# mosfets.net
KiCad netlist of a schematic drawn in EAGLE
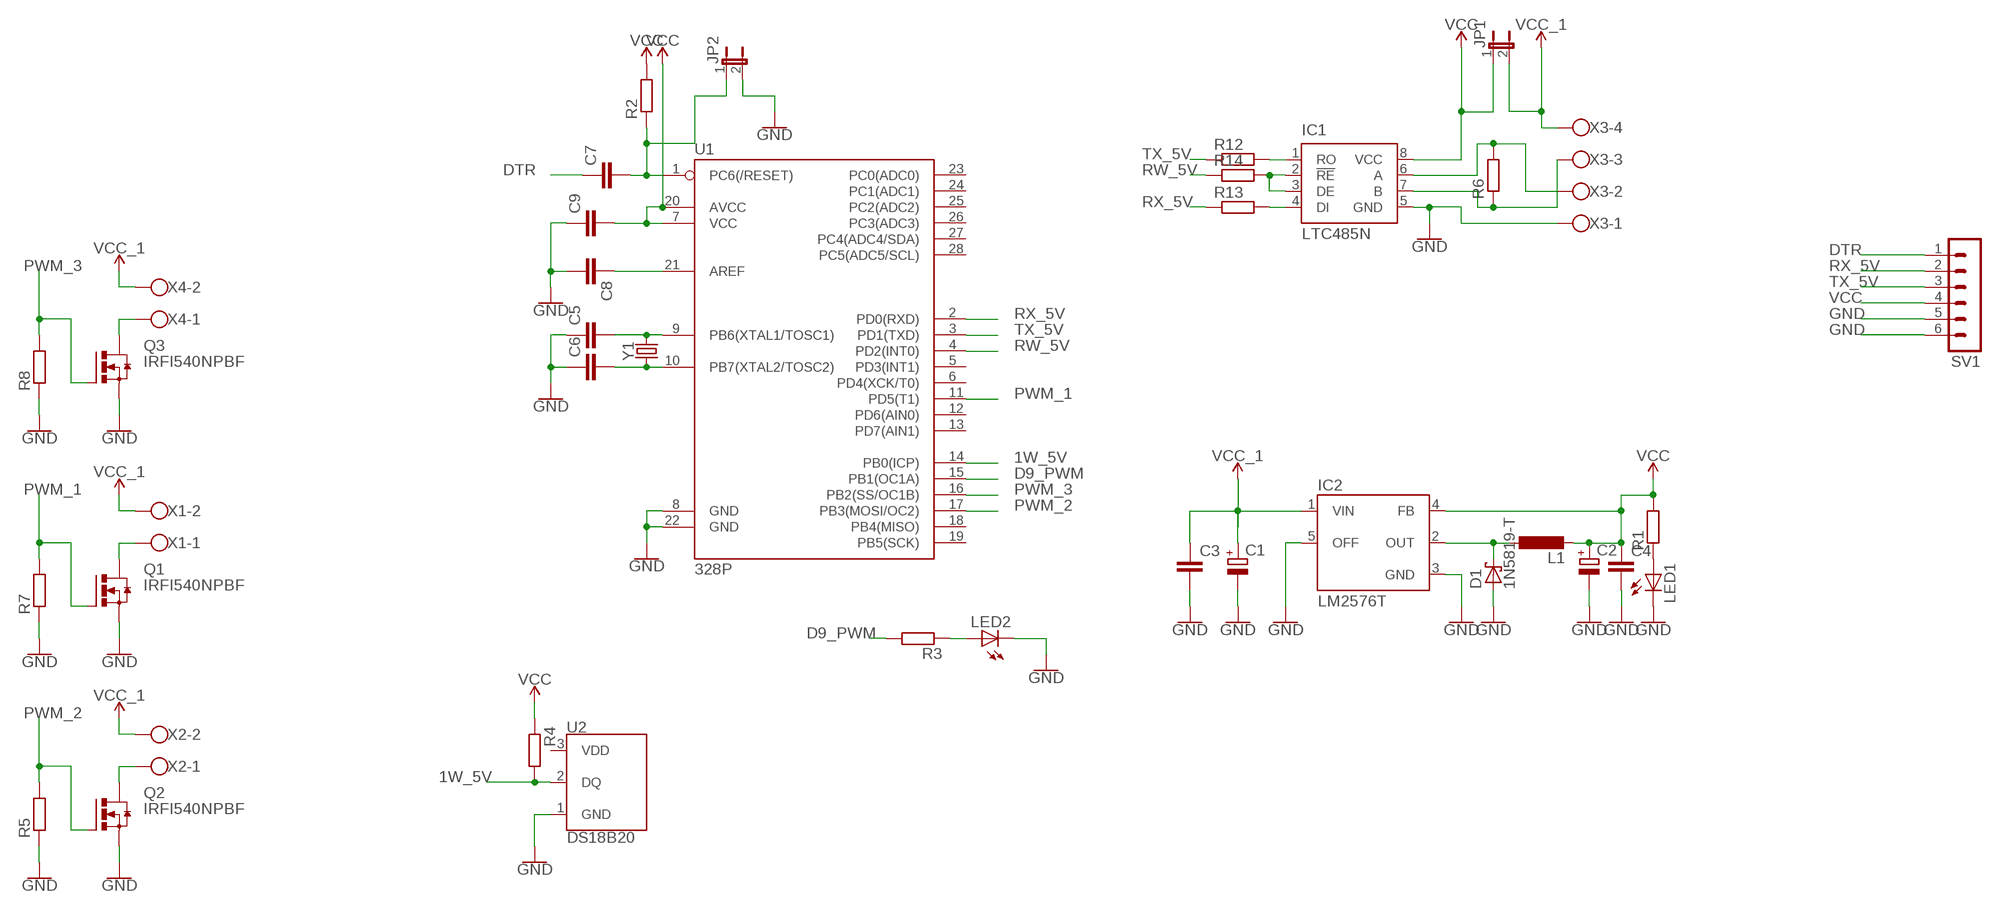
[diagram p0: schematic, sheet 1]

(export (version "E")
  (design (tool "Eeschema 10.0.6"))
  (components
    (comp (ref "C1")
      (value "CPOL-EUE5-10.5")
      (footprint "eagle-import:E5-10,5")
      (libsource (lib "eagle-import") (part "CPOL-EUE5-10.5"))
    )
    (comp (ref "C2")
      (value "CPOL-EUE5-10.5")
      (footprint "eagle-import:E5-10,5")
      (libsource (lib "eagle-import") (part "CPOL-EUE5-10.5"))
    )
    (comp (ref "C3")
      (value "C-EU025-025X050")
      (footprint "eagle-import:C025-025X050")
      (libsource (lib "eagle-import") (part "C-EU025-025X050"))
    )
    (comp (ref "C4")
      (value "C-EU025-025X050")
      (footprint "eagle-import:C025-025X050")
      (libsource (lib "eagle-import") (part "C-EU025-025X050"))
    )
    (comp (ref "C5")
      (value "C-EU025-025X050")
      (footprint "eagle-import:C025-025X050")
      (libsource (lib "eagle-import") (part "C-EU025-025X050"))
    )
    (comp (ref "C6")
      (value "C-EU025-025X050")
      (footprint "eagle-import:C025-025X050")
      (libsource (lib "eagle-import") (part "C-EU025-025X050"))
    )
    (comp (ref "C7")
      (value "C-EU025-025X050")
      (footprint "eagle-import:C025-025X050")
      (libsource (lib "eagle-import") (part "C-EU025-025X050"))
    )
    (comp (ref "C8")
      (value "C-EU025-025X050")
      (footprint "eagle-import:C025-025X050")
      (libsource (lib "eagle-import") (part "C-EU025-025X050"))
    )
    (comp (ref "C9")
      (value "C-EU025-025X050")
      (footprint "eagle-import:C025-025X050")
      (libsource (lib "eagle-import") (part "C-EU025-025X050"))
    )
    (comp (ref "D1")
      (value "1N5819-T")
      (footprint "eagle-import:DO41-7.6")
      (libsource (lib "eagle-import") (part "1N5819-T"))
    )
    (comp (ref "IC1")
      (value "LTC485N")
      (footprint "eagle-import:DIL08")
      (libsource (lib "eagle-import") (part "LTC485N"))
    )
    (comp (ref "IC2")
      (value "LM2576T")
      (footprint "eagle-import:TO220-5")
      (libsource (lib "eagle-import") (part "LM2576T"))
    )
    (comp (ref "JP1")
      (value "JP1E")
      (footprint "eagle-import:JP1")
      (libsource (lib "eagle-import") (part "JP1E"))
    )
    (comp (ref "JP2")
      (value "JP1E")
      (footprint "eagle-import:JP1")
      (libsource (lib "eagle-import") (part "JP1E"))
    )
    (comp (ref "L1")
      (value "L-EUTJ3-U1")
      (footprint "eagle-import:TJ3-U1")
      (libsource (lib "eagle-import") (part "L-EUTJ3-U1"))
    )
    (comp (ref "LED1")
      (value "LED5MM")
      (footprint "eagle-import:LED5MM")
      (libsource (lib "eagle-import") (part "LED5MM"))
    )
    (comp (ref "LED2")
      (value "LED5MM")
      (footprint "eagle-import:LED5MM")
      (libsource (lib "eagle-import") (part "LED5MM"))
    )
    (comp (ref "Q1")
      (value "IRFI540NPBF")
      (footprint "eagle-import:TO220BH")
      (libsource (lib "eagle-import") (part "IRFI540NPBF"))
    )
    (comp (ref "Q2")
      (value "IRFI540NPBF")
      (footprint "eagle-import:TO220BH")
      (libsource (lib "eagle-import") (part "IRFI540NPBF"))
    )
    (comp (ref "Q3")
      (value "IRFI540NPBF")
      (footprint "eagle-import:TO220BH")
      (libsource (lib "eagle-import") (part "IRFI540NPBF"))
    )
    (comp (ref "R1")
      (value "R-EU_0204/7")
      (footprint "eagle-import:0204_7")
      (libsource (lib "eagle-import") (part "R-EU_0204/7"))
    )
    (comp (ref "R2")
      (value "R-EU_0204/7")
      (footprint "eagle-import:0204_7")
      (libsource (lib "eagle-import") (part "R-EU_0204/7"))
    )
    (comp (ref "R3")
      (value "R-EU_0204/7")
      (footprint "eagle-import:0204_7")
      (libsource (lib "eagle-import") (part "R-EU_0204/7"))
    )
    (comp (ref "R4")
      (value "R-EU_0204/7")
      (footprint "eagle-import:0204_7")
      (libsource (lib "eagle-import") (part "R-EU_0204/7"))
    )
    (comp (ref "R5")
      (value "R-EU_0204/7")
      (footprint "eagle-import:0204_7")
      (libsource (lib "eagle-import") (part "R-EU_0204/7"))
    )
    (comp (ref "R6")
      (value "R-EU_0204/7")
      (footprint "eagle-import:0204_7")
      (libsource (lib "eagle-import") (part "R-EU_0204/7"))
    )
    (comp (ref "R7")
      (value "R-EU_0204/7")
      (footprint "eagle-import:0204_7")
      (libsource (lib "eagle-import") (part "R-EU_0204/7"))
    )
    (comp (ref "R8")
      (value "R-EU_0204/7")
      (footprint "eagle-import:0204_7")
      (libsource (lib "eagle-import") (part "R-EU_0204/7"))
    )
    (comp (ref "R12")
      (value "R-EU_0204/7")
      (footprint "eagle-import:0204_7")
      (libsource (lib "eagle-import") (part "R-EU_0204/7"))
    )
    (comp (ref "R13")
      (value "R-EU_0204/7")
      (footprint "eagle-import:0204_7")
      (libsource (lib "eagle-import") (part "R-EU_0204/7"))
    )
    (comp (ref "R14")
      (value "R-EU_0204/7")
      (footprint "eagle-import:0204_7")
      (libsource (lib "eagle-import") (part "R-EU_0204/7"))
    )
    (comp (ref "SV1")
      (value "MA06-1")
      (footprint "eagle-import:MA06-1")
      (libsource (lib "eagle-import") (part "MA06-1"))
    )
    (comp (ref "U1")
      (value "328P")
      (footprint "eagle-import:DIP28")
      (libsource (lib "eagle-import") (part "ATMEGA328P_PDIP"))
    )
    (comp (ref "U2")
      (value "DS18B20")
      (footprint "eagle-import:TO-92-AMMO")
      (libsource (lib "eagle-import") (part "DS18B20"))
    )
    (comp (ref "X1")
      (value "W237-102")
      (footprint "eagle-import:W237-102")
      (fields (field (name "MPN") "237-102"))
      (libsource (lib "eagle-import") (part "W237-102"))
    )
    (comp (ref "X2")
      (value "W237-102")
      (footprint "eagle-import:W237-102")
      (fields (field (name "MPN") "237-102"))
      (libsource (lib "eagle-import") (part "W237-102"))
    )
    (comp (ref "X3")
      (value "W237-4")
      (footprint "eagle-import:W237-4")
      (libsource (lib "eagle-import") (part "W237-4"))
    )
    (comp (ref "X4")
      (value "W237-102")
      (footprint "eagle-import:W237-102")
      (fields (field (name "MPN") "237-102"))
      (libsource (lib "eagle-import") (part "W237-102"))
    )
    (comp (ref "Y1")
      (value "CRYSTALPTH-HC49US")
      (footprint "eagle-import:HC49US")
      (libsource (lib "eagle-import") (part "CRYSTALPTH-HC49US"))
    )
  )
  (nets
    (net (code "1") (name "/1W_5V") (class "Default")
      (node (ref "R4") (pin "2") (pinfunction "2_2") (pintype "passive"))
      (node (ref "U1") (pin "14") (pinfunction "PB0(ICP)_14") (pintype "bidirectional"))
      (node (ref "U2") (pin "2") (pinfunction "DQ_2") (pintype "bidirectional"))
    )
    (net (code "2") (name "/D9_PWM") (class "Default")
      (node (ref "R3") (pin "2") (pinfunction "2_2") (pintype "passive"))
      (node (ref "U1") (pin "15") (pinfunction "PB1(OC1A)_15") (pintype "bidirectional"))
    )
    (net (code "3") (name "/DTR") (class "Default")
      (node (ref "C7") (pin "1") (pinfunction "1_1") (pintype "passive"))
      (node (ref "SV1") (pin "1") (pinfunction "1_1") (pintype "passive"))
    )
    (net (code "4") (name "/PWM_1") (class "Default")
      (node (ref "Q1") (pin "G") (pinfunction "G_G") (pintype "passive"))
      (node (ref "R7") (pin "2") (pinfunction "2_2") (pintype "passive"))
      (node (ref "U1") (pin "11") (pinfunction "PD5(T1)_11") (pintype "bidirectional"))
    )
    (net (code "5") (name "/PWM_2") (class "Default")
      (node (ref "Q2") (pin "G") (pinfunction "G_G") (pintype "passive"))
      (node (ref "R5") (pin "2") (pinfunction "2_2") (pintype "passive"))
      (node (ref "U1") (pin "17") (pinfunction "PB3(MOSI/OC2)_17") (pintype "bidirectional"))
    )
    (net (code "6") (name "/PWM_3") (class "Default")
      (node (ref "Q3") (pin "G") (pinfunction "G_G") (pintype "passive"))
      (node (ref "R8") (pin "2") (pinfunction "2_2") (pintype "passive"))
      (node (ref "U1") (pin "16") (pinfunction "PB2(SS/OC1B)_16") (pintype "bidirectional"))
    )
    (net (code "7") (name "/RW_5V") (class "Default")
      (node (ref "R14") (pin "1") (pinfunction "1_1") (pintype "passive"))
      (node (ref "U1") (pin "4") (pinfunction "PD2(INT0)_4") (pintype "bidirectional"))
    )
    (net (code "8") (name "/RX_5V") (class "Default")
      (node (ref "R13") (pin "1") (pinfunction "1_1") (pintype "passive"))
      (node (ref "SV1") (pin "2") (pinfunction "2_2") (pintype "passive"))
      (node (ref "U1") (pin "2") (pinfunction "PD0(RXD)_2") (pintype "bidirectional"))
    )
    (net (code "9") (name "/TX_5V") (class "Default")
      (node (ref "R12") (pin "1") (pinfunction "1_1") (pintype "passive"))
      (node (ref "SV1") (pin "3") (pinfunction "3_3") (pintype "passive"))
      (node (ref "U1") (pin "3") (pinfunction "PD1(TXD)_3") (pintype "bidirectional"))
    )
    (net (code "10") (name "/VDD") (class "Default")
      (node (ref "U2") (pin "3") (pinfunction "VDD_3") (pintype "power_in"))
    )
    (net (code "11") (name "GND") (class "Default")
      (node (ref "C1") (pin "-") (pinfunction "-_-") (pintype "passive"))
      (node (ref "C2") (pin "-") (pinfunction "-_-") (pintype "passive"))
      (node (ref "C3") (pin "2") (pinfunction "2_2") (pintype "passive"))
      (node (ref "C4") (pin "2") (pinfunction "2_2") (pintype "passive"))
      (node (ref "C5") (pin "1") (pinfunction "1_1") (pintype "passive"))
      (node (ref "C6") (pin "1") (pinfunction "1_1") (pintype "passive"))
      (node (ref "C8") (pin "2") (pinfunction "2_2") (pintype "passive"))
      (node (ref "C9") (pin "1") (pinfunction "1_1") (pintype "passive"))
      (node (ref "D1") (pin "A") (pinfunction "A_A") (pintype "passive"))
      (node (ref "IC1") (pin "5") (pinfunction "GND_5") (pintype "input"))
      (node (ref "IC2") (pin "3") (pinfunction "GND_3") (pintype "power_in"))
      (node (ref "IC2") (pin "5") (pinfunction "OFF_5") (pintype "input"))
      (node (ref "JP2") (pin "2") (pinfunction "2_2") (pintype "passive"))
      (node (ref "LED1") (pin "K") (pinfunction "C_K") (pintype "passive"))
      (node (ref "LED2") (pin "K") (pinfunction "C_K") (pintype "passive"))
      (node (ref "Q1") (pin "S") (pinfunction "S_S") (pintype "passive"))
      (node (ref "Q2") (pin "S") (pinfunction "S_S") (pintype "passive"))
      (node (ref "Q3") (pin "S") (pinfunction "S_S") (pintype "passive"))
      (node (ref "R5") (pin "1") (pinfunction "1_1") (pintype "passive"))
      (node (ref "R7") (pin "1") (pinfunction "1_1") (pintype "passive"))
      (node (ref "R8") (pin "1") (pinfunction "1_1") (pintype "passive"))
      (node (ref "SV1") (pin "5") (pinfunction "5_5") (pintype "passive"))
      (node (ref "SV1") (pin "6") (pinfunction "6_6") (pintype "passive"))
      (node (ref "U1") (pin "22") (pinfunction "GND_22") (pintype "bidirectional"))
      (node (ref "U1") (pin "8") (pinfunction "GND_8") (pintype "bidirectional"))
      (node (ref "U2") (pin "1") (pinfunction "GND_1") (pintype "power_in"))
      (node (ref "X3") (pin "1") (pinfunction "KL_1") (pintype "passive"))
    )
    (net (code "12") (name "Net-(IC1-A)") (class "Default")
      (node (ref "IC1") (pin "6") (pinfunction "A_6") (pintype "bidirectional"))
      (node (ref "R6") (pin "2") (pinfunction "2_2") (pintype "passive"))
      (node (ref "X3") (pin "2") (pinfunction "KL_2") (pintype "passive"))
    )
    (net (code "13") (name "Net-(IC1-B)") (class "Default")
      (node (ref "IC1") (pin "7") (pinfunction "B_7") (pintype "bidirectional"))
      (node (ref "R6") (pin "1") (pinfunction "1_1") (pintype "passive"))
      (node (ref "X3") (pin "3") (pinfunction "KL_3") (pintype "passive"))
    )
    (net (code "14") (name "Net-(IC1-DE)") (class "Default")
      (node (ref "IC1") (pin "2") (pinfunction "~{RE}_2") (pintype "input"))
      (node (ref "IC1") (pin "3") (pinfunction "DE_3") (pintype "input"))
      (node (ref "R14") (pin "2") (pinfunction "2_2") (pintype "passive"))
    )
    (net (code "15") (name "Net-(IC1-DI)") (class "Default")
      (node (ref "IC1") (pin "4") (pinfunction "DI_4") (pintype "input"))
      (node (ref "R13") (pin "2") (pinfunction "2_2") (pintype "passive"))
    )
    (net (code "16") (name "Net-(IC1-RO)") (class "Default")
      (node (ref "IC1") (pin "1") (pinfunction "RO_1") (pintype "output"))
      (node (ref "R12") (pin "2") (pinfunction "2_2") (pintype "passive"))
    )
    (net (code "17") (name "Net-(IC2-OUT)") (class "Default")
      (node (ref "D1") (pin "C") (pinfunction "C_C") (pintype "passive"))
      (node (ref "IC2") (pin "2") (pinfunction "OUT_2") (pintype "output"))
      (node (ref "L1") (pin "1") (pinfunction "1_1") (pintype "passive"))
    )
    (net (code "18") (name "Net-(LED1-PadA)") (class "Default")
      (node (ref "LED1") (pin "A") (pinfunction "A_A") (pintype "passive"))
      (node (ref "R1") (pin "1") (pinfunction "1_1") (pintype "passive"))
    )
    (net (code "19") (name "Net-(LED2-PadA)") (class "Default")
      (node (ref "LED2") (pin "A") (pinfunction "A_A") (pintype "passive"))
      (node (ref "R3") (pin "1") (pinfunction "1_1") (pintype "passive"))
    )
    (net (code "20") (name "Net-(U1-AREF)") (class "Default")
      (node (ref "C8") (pin "1") (pinfunction "1_1") (pintype "passive"))
      (node (ref "U1") (pin "21") (pinfunction "AREF_21") (pintype "bidirectional"))
    )
    (net (code "21") (name "Net-(U1-PB6(XTAL1{slash}TOSC1))") (class "Default")
      (node (ref "C5") (pin "2") (pinfunction "2_2") (pintype "passive"))
      (node (ref "U1") (pin "9") (pinfunction "PB6(XTAL1/TOSC1)_9") (pintype "bidirectional"))
      (node (ref "Y1") (pin "2") (pinfunction "2_2") (pintype "passive"))
    )
    (net (code "22") (name "Net-(U1-PB7(XTAL2{slash}TOSC2))") (class "Default")
      (node (ref "C6") (pin "2") (pinfunction "2_2") (pintype "passive"))
      (node (ref "U1") (pin "10") (pinfunction "PB7(XTAL2/TOSC2)_10") (pintype "bidirectional"))
      (node (ref "Y1") (pin "1") (pinfunction "1_1") (pintype "passive"))
    )
    (net (code "23") (name "Net-(U1-PC6({slash}RESET))") (class "Default")
      (node (ref "C7") (pin "2") (pinfunction "2_2") (pintype "passive"))
      (node (ref "JP2") (pin "1") (pinfunction "1_1") (pintype "passive"))
      (node (ref "R2") (pin "1") (pinfunction "1_1") (pintype "passive"))
      (node (ref "U1") (pin "1") (pinfunction "PC6(/RESET)_1") (pintype "bidirectional"))
    )
    (net (code "24") (name "Net-(X1A-KL)") (class "Default")
      (node (ref "Q1") (pin "D") (pinfunction "D_D") (pintype "passive"))
      (node (ref "X1") (pin "1") (pinfunction "KL_1") (pintype "passive"))
    )
    (net (code "25") (name "Net-(X2A-KL)") (class "Default")
      (node (ref "Q2") (pin "D") (pinfunction "D_D") (pintype "passive"))
      (node (ref "X2") (pin "1") (pinfunction "KL_1") (pintype "passive"))
    )
    (net (code "26") (name "Net-(X4A-KL)") (class "Default")
      (node (ref "Q3") (pin "D") (pinfunction "D_D") (pintype "passive"))
      (node (ref "X4") (pin "1") (pinfunction "KL_1") (pintype "passive"))
    )
    (net (code "27") (name "VCC") (class "Default")
      (node (ref "C2") (pin "+") (pinfunction "+_+") (pintype "passive"))
      (node (ref "C4") (pin "1") (pinfunction "1_1") (pintype "passive"))
      (node (ref "C9") (pin "2") (pinfunction "2_2") (pintype "passive"))
      (node (ref "IC1") (pin "8") (pinfunction "VCC_8") (pintype "input"))
      (node (ref "IC2") (pin "4") (pinfunction "FB_4") (pintype "input"))
      (node (ref "JP1") (pin "1") (pinfunction "1_1") (pintype "passive"))
      (node (ref "L1") (pin "2") (pinfunction "2_2") (pintype "passive"))
      (node (ref "R1") (pin "2") (pinfunction "2_2") (pintype "passive"))
      (node (ref "R2") (pin "2") (pinfunction "2_2") (pintype "passive"))
      (node (ref "R4") (pin "1") (pinfunction "1_1") (pintype "passive"))
      (node (ref "SV1") (pin "4") (pinfunction "4_4") (pintype "passive"))
      (node (ref "U1") (pin "20") (pinfunction "AVCC_20") (pintype "bidirectional"))
      (node (ref "U1") (pin "7") (pinfunction "VCC_7") (pintype "bidirectional"))
    )
    (net (code "28") (name "VCC_1") (class "Default")
      (node (ref "C1") (pin "+") (pinfunction "+_+") (pintype "passive"))
      (node (ref "C3") (pin "1") (pinfunction "1_1") (pintype "passive"))
      (node (ref "IC2") (pin "1") (pinfunction "VIN_1") (pintype "power_in"))
      (node (ref "JP1") (pin "2") (pinfunction "2_2") (pintype "passive"))
      (node (ref "X1") (pin "2") (pinfunction "KL_2") (pintype "passive"))
      (node (ref "X2") (pin "2") (pinfunction "KL_2") (pintype "passive"))
      (node (ref "X3") (pin "4") (pinfunction "KL_4") (pintype "passive"))
      (node (ref "X4") (pin "2") (pinfunction "KL_2") (pintype "passive"))
    )
    (net (code "29") (name "unconnected-(U1-PB4(MISO)-Pad18)") (class "Default")
      (node (ref "U1") (pin "18") (pinfunction "PB4(MISO)_18") (pintype "bidirectional"))
    )
    (net (code "30") (name "unconnected-(U1-PB5(SCK)-Pad19)") (class "Default")
      (node (ref "U1") (pin "19") (pinfunction "PB5(SCK)_19") (pintype "bidirectional"))
    )
    (net (code "31") (name "unconnected-(U1-PC0(ADC0)-Pad23)") (class "Default")
      (node (ref "U1") (pin "23") (pinfunction "PC0(ADC0)_23") (pintype "bidirectional"))
    )
    (net (code "32") (name "unconnected-(U1-PC1(ADC1)-Pad24)") (class "Default")
      (node (ref "U1") (pin "24") (pinfunction "PC1(ADC1)_24") (pintype "bidirectional"))
    )
    (net (code "33") (name "unconnected-(U1-PC2(ADC2)-Pad25)") (class "Default")
      (node (ref "U1") (pin "25") (pinfunction "PC2(ADC2)_25") (pintype "bidirectional"))
    )
    (net (code "34") (name "unconnected-(U1-PC3(ADC3)-Pad26)") (class "Default")
      (node (ref "U1") (pin "26") (pinfunction "PC3(ADC3)_26") (pintype "bidirectional"))
    )
    (net (code "35") (name "unconnected-(U1-PC4(ADC4{slash}SDA)-Pad27)") (class "Default")
      (node (ref "U1") (pin "27") (pinfunction "PC4(ADC4/SDA)_27") (pintype "bidirectional"))
    )
    (net (code "36") (name "unconnected-(U1-PC5(ADC5{slash}SCL)-Pad28)") (class "Default")
      (node (ref "U1") (pin "28") (pinfunction "PC5(ADC5/SCL)_28") (pintype "bidirectional"))
    )
    (net (code "37") (name "unconnected-(U1-PD3(INT1)-Pad5)") (class "Default")
      (node (ref "U1") (pin "5") (pinfunction "PD3(INT1)_5") (pintype "bidirectional"))
    )
    (net (code "38") (name "unconnected-(U1-PD4(XCK{slash}T0)-Pad6)") (class "Default")
      (node (ref "U1") (pin "6") (pinfunction "PD4(XCK/T0)_6") (pintype "bidirectional"))
    )
    (net (code "39") (name "unconnected-(U1-PD6(AIN0)-Pad12)") (class "Default")
      (node (ref "U1") (pin "12") (pinfunction "PD6(AIN0)_12") (pintype "bidirectional"))
    )
    (net (code "40") (name "unconnected-(U1-PD7(AIN1)-Pad13)") (class "Default")
      (node (ref "U1") (pin "13") (pinfunction "PD7(AIN1)_13") (pintype "bidirectional"))
    )
  )
)
